# 4ChannelSlidePotBoard.net
KiCad netlist of a schematic drawn in EAGLE
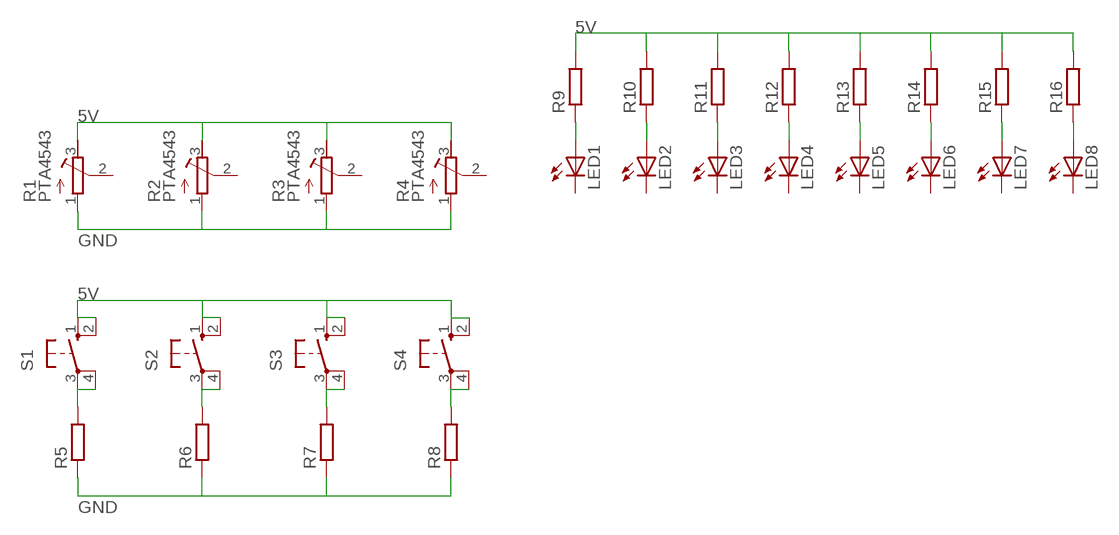
[diagram p0: schematic, sheet 1]

(export (version "E")
  (design (tool "Eeschema 10.0.6"))
  (components
    (comp (ref "LED1")
      (value "LED3MM")
      (footprint "eagle-import:LED3MM")
      (libsource (lib "eagle-import") (part "LED3MM"))
    )
    (comp (ref "LED2")
      (value "LED3MM")
      (footprint "eagle-import:LED3MM")
      (libsource (lib "eagle-import") (part "LED3MM"))
    )
    (comp (ref "LED3")
      (value "LED3MM")
      (footprint "eagle-import:LED3MM")
      (libsource (lib "eagle-import") (part "LED3MM"))
    )
    (comp (ref "LED4")
      (value "LED3MM")
      (footprint "eagle-import:LED3MM")
      (libsource (lib "eagle-import") (part "LED3MM"))
    )
    (comp (ref "LED5")
      (value "LED3MM")
      (footprint "eagle-import:LED3MM")
      (libsource (lib "eagle-import") (part "LED3MM"))
    )
    (comp (ref "LED6")
      (value "LED3MM")
      (footprint "eagle-import:LED3MM")
      (libsource (lib "eagle-import") (part "LED3MM"))
    )
    (comp (ref "LED7")
      (value "LED3MM")
      (footprint "eagle-import:LED3MM")
      (libsource (lib "eagle-import") (part "LED3MM"))
    )
    (comp (ref "LED8")
      (value "LED3MM")
      (footprint "eagle-import:LED3MM")
      (libsource (lib "eagle-import") (part "LED3MM"))
    )
    (comp (ref "R1")
      (value "PTA4543")
      (footprint "eagle-import:4543")
      (libsource (lib "eagle-import") (part "PTA4543"))
    )
    (comp (ref "R2")
      (value "PTA4543")
      (footprint "eagle-import:4543")
      (libsource (lib "eagle-import") (part "PTA4543"))
    )
    (comp (ref "R3")
      (value "PTA4543")
      (footprint "eagle-import:4543")
      (libsource (lib "eagle-import") (part "PTA4543"))
    )
    (comp (ref "R4")
      (value "PTA4543")
      (footprint "eagle-import:4543")
      (libsource (lib "eagle-import") (part "PTA4543"))
    )
    (comp (ref "R5")
      (value "R-EU_R1206")
      (footprint "eagle-import:R1206")
      (libsource (lib "eagle-import") (part "R-EU_R1206"))
    )
    (comp (ref "R6")
      (value "R-EU_R1206")
      (footprint "eagle-import:R1206")
      (libsource (lib "eagle-import") (part "R-EU_R1206"))
    )
    (comp (ref "R7")
      (value "R-EU_R1206")
      (footprint "eagle-import:R1206")
      (libsource (lib "eagle-import") (part "R-EU_R1206"))
    )
    (comp (ref "R8")
      (value "R-EU_R1206")
      (footprint "eagle-import:R1206")
      (libsource (lib "eagle-import") (part "R-EU_R1206"))
    )
    (comp (ref "R9")
      (value "R-EU_R1206")
      (footprint "eagle-import:R1206")
      (libsource (lib "eagle-import") (part "R-EU_R1206"))
    )
    (comp (ref "R10")
      (value "R-EU_R1206")
      (footprint "eagle-import:R1206")
      (libsource (lib "eagle-import") (part "R-EU_R1206"))
    )
    (comp (ref "R11")
      (value "R-EU_R1206")
      (footprint "eagle-import:R1206")
      (libsource (lib "eagle-import") (part "R-EU_R1206"))
    )
    (comp (ref "R12")
      (value "R-EU_R1206")
      (footprint "eagle-import:R1206")
      (libsource (lib "eagle-import") (part "R-EU_R1206"))
    )
    (comp (ref "R13")
      (value "R-EU_R1206")
      (footprint "eagle-import:R1206")
      (libsource (lib "eagle-import") (part "R-EU_R1206"))
    )
    (comp (ref "R14")
      (value "R-EU_R1206")
      (footprint "eagle-import:R1206")
      (libsource (lib "eagle-import") (part "R-EU_R1206"))
    )
    (comp (ref "R15")
      (value "R-EU_R1206")
      (footprint "eagle-import:R1206")
      (libsource (lib "eagle-import") (part "R-EU_R1206"))
    )
    (comp (ref "R16")
      (value "R-EU_R1206")
      (footprint "eagle-import:R1206")
      (libsource (lib "eagle-import") (part "R-EU_R1206"))
    )
    (comp (ref "S1")
      (value "40-XX")
      (footprint "eagle-import:B3F-40XX")
      (fields (field (name "MF") "OMRON COMPONENTS USA") (field (name "MPN") "B3F-4000"))
      (libsource (lib "eagle-import") (part "40-XX"))
    )
    (comp (ref "S2")
      (value "40-XX")
      (footprint "eagle-import:B3F-40XX")
      (fields (field (name "MF") "OMRON COMPONENTS USA") (field (name "MPN") "B3F-4000"))
      (libsource (lib "eagle-import") (part "40-XX"))
    )
    (comp (ref "S3")
      (value "40-XX")
      (footprint "eagle-import:B3F-40XX")
      (fields (field (name "MF") "OMRON COMPONENTS USA") (field (name "MPN") "B3F-4000"))
      (libsource (lib "eagle-import") (part "40-XX"))
    )
    (comp (ref "S4")
      (value "40-XX")
      (footprint "eagle-import:B3F-40XX")
      (fields (field (name "MF") "OMRON COMPONENTS USA") (field (name "MPN") "B3F-4000"))
      (libsource (lib "eagle-import") (part "40-XX"))
    )
  )
  (nets
    (net (code "1") (name "/5V") (class "Default")
      (node (ref "R1") (pin "3") (pinfunction "3_3") (pintype "passive"))
      (node (ref "R10") (pin "2") (pinfunction "2_2") (pintype "passive"))
      (node (ref "R11") (pin "2") (pinfunction "2_2") (pintype "passive"))
      (node (ref "R12") (pin "2") (pinfunction "2_2") (pintype "passive"))
      (node (ref "R13") (pin "2") (pinfunction "2_2") (pintype "passive"))
      (node (ref "R14") (pin "2") (pinfunction "2_2") (pintype "passive"))
      (node (ref "R15") (pin "2") (pinfunction "2_2") (pintype "passive"))
      (node (ref "R16") (pin "2") (pinfunction "2_2") (pintype "passive"))
      (node (ref "R2") (pin "3") (pinfunction "3_3") (pintype "passive"))
      (node (ref "R3") (pin "3") (pinfunction "3_3") (pintype "passive"))
      (node (ref "R4") (pin "3") (pinfunction "3_3") (pintype "passive"))
      (node (ref "R9") (pin "2") (pinfunction "2_2") (pintype "passive"))
      (node (ref "S1") (pin "1") (pinfunction "S_1") (pintype "passive"))
      (node (ref "S1") (pin "2") (pinfunction "S1_2") (pintype "passive"))
      (node (ref "S2") (pin "1") (pinfunction "S_1") (pintype "passive"))
      (node (ref "S2") (pin "2") (pinfunction "S1_2") (pintype "passive"))
      (node (ref "S3") (pin "1") (pinfunction "S_1") (pintype "passive"))
      (node (ref "S3") (pin "2") (pinfunction "S1_2") (pintype "passive"))
      (node (ref "S4") (pin "1") (pinfunction "S_1") (pintype "passive"))
      (node (ref "S4") (pin "2") (pinfunction "S1_2") (pintype "passive"))
    )
    (net (code "2") (name "/GND") (class "Default")
      (node (ref "R1") (pin "1") (pinfunction "1_1") (pintype "passive"))
      (node (ref "R2") (pin "1") (pinfunction "1_1") (pintype "passive"))
      (node (ref "R3") (pin "1") (pinfunction "1_1") (pintype "passive"))
      (node (ref "R4") (pin "1") (pinfunction "1_1") (pintype "passive"))
      (node (ref "R5") (pin "1") (pinfunction "1_1") (pintype "passive"))
      (node (ref "R6") (pin "1") (pinfunction "1_1") (pintype "passive"))
      (node (ref "R7") (pin "1") (pinfunction "1_1") (pintype "passive"))
      (node (ref "R8") (pin "1") (pinfunction "1_1") (pintype "passive"))
    )
    (net (code "3") (name "Net-(LED1-PadA)") (class "Default")
      (node (ref "LED1") (pin "A") (pinfunction "A_A") (pintype "passive"))
      (node (ref "R9") (pin "1") (pinfunction "1_1") (pintype "passive"))
    )
    (net (code "4") (name "Net-(LED2-PadA)") (class "Default")
      (node (ref "LED2") (pin "A") (pinfunction "A_A") (pintype "passive"))
      (node (ref "R10") (pin "1") (pinfunction "1_1") (pintype "passive"))
    )
    (net (code "5") (name "Net-(LED3-PadA)") (class "Default")
      (node (ref "LED3") (pin "A") (pinfunction "A_A") (pintype "passive"))
      (node (ref "R11") (pin "1") (pinfunction "1_1") (pintype "passive"))
    )
    (net (code "6") (name "Net-(LED4-PadA)") (class "Default")
      (node (ref "LED4") (pin "A") (pinfunction "A_A") (pintype "passive"))
      (node (ref "R12") (pin "1") (pinfunction "1_1") (pintype "passive"))
    )
    (net (code "7") (name "Net-(LED5-PadA)") (class "Default")
      (node (ref "LED5") (pin "A") (pinfunction "A_A") (pintype "passive"))
      (node (ref "R13") (pin "1") (pinfunction "1_1") (pintype "passive"))
    )
    (net (code "8") (name "Net-(LED6-PadA)") (class "Default")
      (node (ref "LED6") (pin "A") (pinfunction "A_A") (pintype "passive"))
      (node (ref "R14") (pin "1") (pinfunction "1_1") (pintype "passive"))
    )
    (net (code "9") (name "Net-(LED7-PadA)") (class "Default")
      (node (ref "LED7") (pin "A") (pinfunction "A_A") (pintype "passive"))
      (node (ref "R15") (pin "1") (pinfunction "1_1") (pintype "passive"))
    )
    (net (code "10") (name "Net-(LED8-PadA)") (class "Default")
      (node (ref "LED8") (pin "A") (pinfunction "A_A") (pintype "passive"))
      (node (ref "R16") (pin "1") (pinfunction "1_1") (pintype "passive"))
    )
    (net (code "11") (name "Net-(S1-P)") (class "Default")
      (node (ref "R5") (pin "2") (pinfunction "2_2") (pintype "passive"))
      (node (ref "S1") (pin "3") (pinfunction "P_3") (pintype "passive"))
      (node (ref "S1") (pin "4") (pinfunction "P1_4") (pintype "passive"))
    )
    (net (code "12") (name "Net-(S2-P)") (class "Default")
      (node (ref "R6") (pin "2") (pinfunction "2_2") (pintype "passive"))
      (node (ref "S2") (pin "3") (pinfunction "P_3") (pintype "passive"))
      (node (ref "S2") (pin "4") (pinfunction "P1_4") (pintype "passive"))
    )
    (net (code "13") (name "Net-(S3-P)") (class "Default")
      (node (ref "R7") (pin "2") (pinfunction "2_2") (pintype "passive"))
      (node (ref "S3") (pin "3") (pinfunction "P_3") (pintype "passive"))
      (node (ref "S3") (pin "4") (pinfunction "P1_4") (pintype "passive"))
    )
    (net (code "14") (name "Net-(S4-P)") (class "Default")
      (node (ref "R8") (pin "2") (pinfunction "2_2") (pintype "passive"))
      (node (ref "S4") (pin "3") (pinfunction "P_3") (pintype "passive"))
      (node (ref "S4") (pin "4") (pinfunction "P1_4") (pintype "passive"))
    )
    (net (code "15") (name "unconnected-(LED1-C-PadK)") (class "Default")
      (node (ref "LED1") (pin "K") (pinfunction "C_K") (pintype "passive"))
    )
    (net (code "16") (name "unconnected-(LED2-C-PadK)") (class "Default")
      (node (ref "LED2") (pin "K") (pinfunction "C_K") (pintype "passive"))
    )
    (net (code "17") (name "unconnected-(LED3-C-PadK)") (class "Default")
      (node (ref "LED3") (pin "K") (pinfunction "C_K") (pintype "passive"))
    )
    (net (code "18") (name "unconnected-(LED4-C-PadK)") (class "Default")
      (node (ref "LED4") (pin "K") (pinfunction "C_K") (pintype "passive"))
    )
    (net (code "19") (name "unconnected-(LED5-C-PadK)") (class "Default")
      (node (ref "LED5") (pin "K") (pinfunction "C_K") (pintype "passive"))
    )
    (net (code "20") (name "unconnected-(LED6-C-PadK)") (class "Default")
      (node (ref "LED6") (pin "K") (pinfunction "C_K") (pintype "passive"))
    )
    (net (code "21") (name "unconnected-(LED7-C-PadK)") (class "Default")
      (node (ref "LED7") (pin "K") (pinfunction "C_K") (pintype "passive"))
    )
    (net (code "22") (name "unconnected-(LED8-C-PadK)") (class "Default")
      (node (ref "LED8") (pin "K") (pinfunction "C_K") (pintype "passive"))
    )
    (net (code "23") (name "unconnected-(R1-Pad2)") (class "Default")
      (node (ref "R1") (pin "2") (pinfunction "2_2") (pintype "passive"))
    )
    (net (code "24") (name "unconnected-(R2-Pad2)") (class "Default")
      (node (ref "R2") (pin "2") (pinfunction "2_2") (pintype "passive"))
    )
    (net (code "25") (name "unconnected-(R3-Pad2)") (class "Default")
      (node (ref "R3") (pin "2") (pinfunction "2_2") (pintype "passive"))
    )
    (net (code "26") (name "unconnected-(R4-Pad2)") (class "Default")
      (node (ref "R4") (pin "2") (pinfunction "2_2") (pintype "passive"))
    )
  )
)
